# OSC.net
KiCad netlist of a schematic drawn in Altium Designer
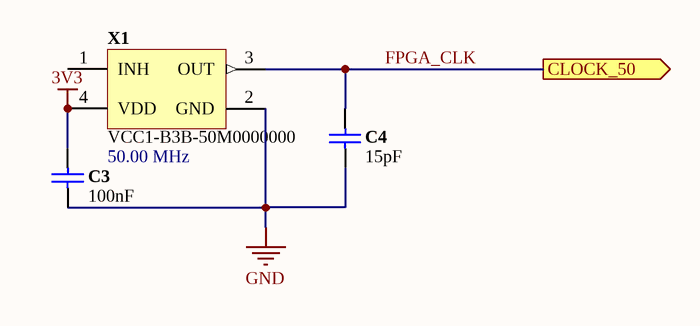
[diagram p0: OSC.SchDoc]

(export (version "E")
  (design (tool "Eeschema 10.0.6"))
  (components
    (comp (ref "C3")
      (value "100nF")
      (footprint "0805C-GENERIC")
      (description "Capacitor, Ceramic, 10% 10V 0805 X7R")
      (fields (field (name "CAPACITANCE") "100nF") (field (name "TOLERANCE") "10 %"))
      (libsource (lib "altium-import") (part "root_0_CAP-NP_"))
    )
    (comp (ref "C4")
      (value "15pF")
      (footprint "0805C-GENERIC")
      (description "Capacitor, Ceramic, 10% 10V 0805 X7R")
      (fields (field (name "CAPACITANCE") "15pF") (field (name "TOLERANCE") "10 %"))
      (libsource (lib "altium-import") (part "root_0_CAP-NP_"))
    )
    (comp (ref "X1")
      (value "VCC1-B3B-50M0000000")
      (footprint "HOSC-L500HW320H105-4_2")
      (description "50 MHz Oscillator, 3.3V, 15pF")
      (fields (field (name "PARTNUMBER") "HCX-C2-20M") (field (name "FREQUENCY") "50.00 MHz"))
      (libsource (lib "Arduino - FPGA Development Board") (part "OSC-4"))
    )
  )
  (nets
    (net (code "1") (name "/FPGA_CLK") (class "Default")
      (node (ref "C4") (pin "1") (pinfunction "1_1") (pintype "passive"))
      (node (ref "X1") (pin "3") (pinfunction "OUT_3") (pintype "output"))
    )
    (net (code "2") (name "3V3") (class "Default")
      (node (ref "C3") (pin "1") (pinfunction "1_1") (pintype "passive"))
      (node (ref "X1") (pin "4") (pinfunction "VDD_4") (pintype "power_in"))
    )
    (net (code "3") (name "GND") (class "Default")
      (node (ref "C3") (pin "2") (pinfunction "2_2") (pintype "passive"))
      (node (ref "C4") (pin "2") (pinfunction "2_2") (pintype "passive"))
      (node (ref "X1") (pin "2") (pinfunction "GND_2") (pintype "power_in"))
    )
    (net (code "4") (name "unconnected-(X1-INH-Pad1)") (class "Default")
      (node (ref "X1") (pin "1") (pinfunction "INH_1") (pintype "open_collector"))
    )
  )
)
